# thermister-led.net
KiCad netlist of a schematic drawn in EAGLE
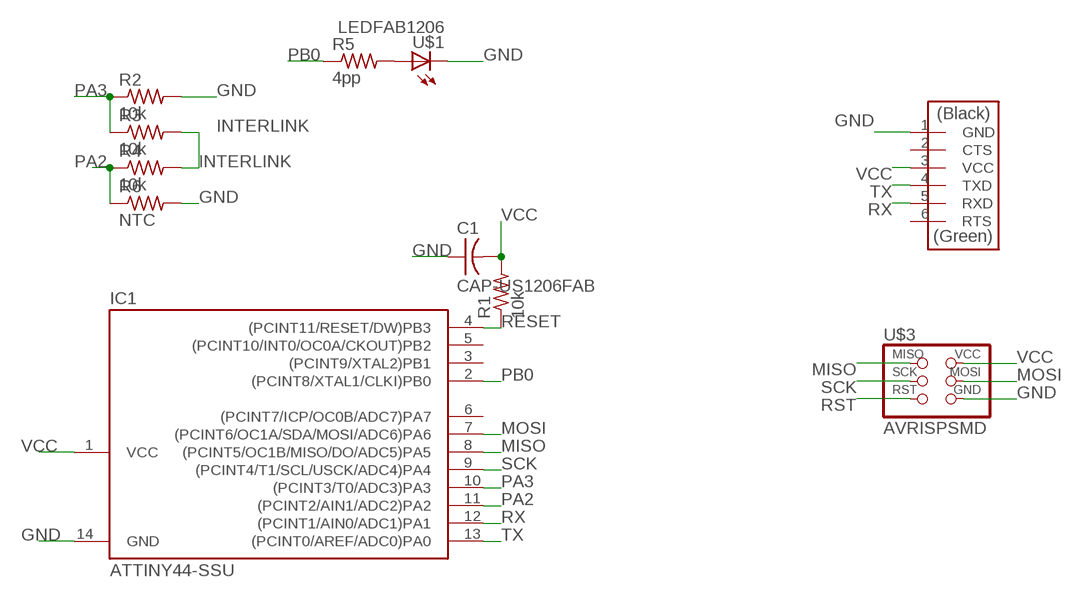
[diagram p0: schematic, sheet 1]

(export (version "E")
  (design (tool "Eeschema 10.0.6"))
  (components
    (comp (ref "C1")
      (value "CAP-US1206FAB")
      (footprint "eagle-import:C1206FAB")
      (libsource (lib "eagle-import") (part "CAP-US1206FAB"))
    )
    (comp (ref "IC1")
      (value "ATTINY44-SSU")
      (footprint "eagle-import:SOIC14")
      (libsource (lib "eagle-import") (part "ATTINY44-SSU"))
    )
    (comp (ref "R1")
      (value "10k")
      (footprint "eagle-import:R1206FAB")
      (libsource (lib "eagle-import") (part "RES-US1206FAB"))
    )
    (comp (ref "R2")
      (value "10k")
      (footprint "eagle-import:R1206FAB")
      (libsource (lib "eagle-import") (part "RES-US1206FAB"))
    )
    (comp (ref "R3")
      (value "10k")
      (footprint "eagle-import:R1206FAB")
      (libsource (lib "eagle-import") (part "RES-US1206FAB"))
    )
    (comp (ref "R4")
      (value "10k")
      (footprint "eagle-import:R1206FAB")
      (libsource (lib "eagle-import") (part "RES-US1206FAB"))
    )
    (comp (ref "R5")
      (value "4pp")
      (footprint "eagle-import:R1206FAB")
      (libsource (lib "eagle-import") (part "RES-US1206FAB"))
    )
    (comp (ref "R6")
      (value "NTC")
      (footprint "eagle-import:R1206FAB")
      (libsource (lib "eagle-import") (part "RES-US1206FAB"))
    )
    (comp (ref "U$1")
      (value "LEDFAB1206")
      (footprint "eagle-import:LED1206FAB")
      (libsource (lib "eagle-import") (part "LEDFAB1206"))
    )
    (comp (ref "U$2")
      (value "FTDI-SMD-HEADER")
      (footprint "eagle-import:1X06SMD")
      (libsource (lib "eagle-import") (part "FTDI-SMD-HEADER"))
    )
    (comp (ref "U$3")
      (value "AVRISPSMD")
      (footprint "eagle-import:2X03SMD")
      (libsource (lib "eagle-import") (part "AVRISPSMD"))
    )
  )
  (nets
    (net (code "1") (name "/GND") (class "Default")
      (node (ref "C1") (pin "1") (pinfunction "1_1") (pintype "passive"))
      (node (ref "IC1") (pin "14") (pinfunction "GND_14") (pintype "power_in"))
      (node (ref "R2") (pin "2") (pinfunction "2_2") (pintype "passive"))
      (node (ref "R6") (pin "2") (pinfunction "2_2") (pintype "passive"))
      (node (ref "U$1") (pin "2") (pinfunction "C_2") (pintype "passive"))
      (node (ref "U$2") (pin "1") (pinfunction "GND_1") (pintype "bidirectional"))
      (node (ref "U$3") (pin "6") (pinfunction "GND_6") (pintype "passive"))
    )
    (net (code "2") (name "/INTERLINK") (class "Default")
      (node (ref "R3") (pin "2") (pinfunction "2_2") (pintype "passive"))
      (node (ref "R4") (pin "2") (pinfunction "2_2") (pintype "passive"))
    )
    (net (code "3") (name "/MISO") (class "Default")
      (node (ref "IC1") (pin "8") (pinfunction "(PCINT5/OC1B/MISO/DO/ADC5)PA5_8") (pintype "bidirectional"))
      (node (ref "U$3") (pin "1") (pinfunction "MISO_1") (pintype "passive"))
    )
    (net (code "4") (name "/MOSI") (class "Default")
      (node (ref "IC1") (pin "7") (pinfunction "(PCINT6/OC1A/SDA/MOSI/ADC6)PA6_7") (pintype "bidirectional"))
      (node (ref "U$3") (pin "4") (pinfunction "MOSI_4") (pintype "passive"))
    )
    (net (code "5") (name "/PA2") (class "Default")
      (node (ref "IC1") (pin "11") (pinfunction "(PCINT2/AIN1/ADC2)PA2_11") (pintype "bidirectional"))
      (node (ref "R4") (pin "1") (pinfunction "1_1") (pintype "passive"))
      (node (ref "R6") (pin "1") (pinfunction "1_1") (pintype "passive"))
    )
    (net (code "6") (name "/PA3") (class "Default")
      (node (ref "IC1") (pin "10") (pinfunction "(PCINT3/T0/ADC3)PA3_10") (pintype "bidirectional"))
      (node (ref "R2") (pin "1") (pinfunction "1_1") (pintype "passive"))
      (node (ref "R3") (pin "1") (pinfunction "1_1") (pintype "passive"))
    )
    (net (code "7") (name "/PB0") (class "Default")
      (node (ref "IC1") (pin "2") (pinfunction "(PCINT8/XTAL1/CLKI)PB0_2") (pintype "bidirectional"))
      (node (ref "R5") (pin "1") (pinfunction "1_1") (pintype "passive"))
    )
    (net (code "8") (name "/RESET") (class "Default")
      (node (ref "IC1") (pin "4") (pinfunction "(PCINT11/RESET/DW)PB3_4") (pintype "bidirectional"))
      (node (ref "R1") (pin "1") (pinfunction "1_1") (pintype "passive"))
    )
    (net (code "9") (name "/RST") (class "Default")
      (node (ref "U$3") (pin "5") (pinfunction "RST_5") (pintype "passive"))
    )
    (net (code "10") (name "/RX") (class "Default")
      (node (ref "IC1") (pin "12") (pinfunction "(PCINT1/AIN0/ADC1)PA1_12") (pintype "bidirectional"))
      (node (ref "U$2") (pin "5") (pinfunction "RXD_5") (pintype "bidirectional"))
    )
    (net (code "11") (name "/SCK") (class "Default")
      (node (ref "IC1") (pin "9") (pinfunction "(PCINT4/T1/SCL/USCK/ADC4)PA4_9") (pintype "bidirectional"))
      (node (ref "U$3") (pin "3") (pinfunction "SCK_3") (pintype "passive"))
    )
    (net (code "12") (name "/TX") (class "Default")
      (node (ref "IC1") (pin "13") (pinfunction "(PCINT0/AREF/ADC0)PA0_13") (pintype "bidirectional"))
      (node (ref "U$2") (pin "4") (pinfunction "TXD_4") (pintype "bidirectional"))
    )
    (net (code "13") (name "/VCC") (class "Default")
      (node (ref "C1") (pin "2") (pinfunction "2_2") (pintype "passive"))
      (node (ref "IC1") (pin "1") (pinfunction "VCC_1") (pintype "power_in"))
      (node (ref "R1") (pin "2") (pinfunction "2_2") (pintype "passive"))
      (node (ref "U$2") (pin "3") (pinfunction "VCC_3") (pintype "bidirectional"))
      (node (ref "U$3") (pin "2") (pinfunction "VCC_2") (pintype "passive"))
    )
    (net (code "14") (name "Net-(U$1-A)") (class "Default")
      (node (ref "R5") (pin "2") (pinfunction "2_2") (pintype "passive"))
      (node (ref "U$1") (pin "1") (pinfunction "A_1") (pintype "passive"))
    )
    (net (code "15") (name "unconnected-(IC1-(PCINT7{slash}ICP{slash}OC0B{slash}ADC7)PA7-Pad6)") (class "Default")
      (node (ref "IC1") (pin "6") (pinfunction "(PCINT7/ICP/OC0B/ADC7)PA7_6") (pintype "bidirectional"))
    )
    (net (code "16") (name "unconnected-(IC1-(PCINT9{slash}XTAL2)PB1-Pad3)") (class "Default")
      (node (ref "IC1") (pin "3") (pinfunction "(PCINT9/XTAL2)PB1_3") (pintype "bidirectional"))
    )
    (net (code "17") (name "unconnected-(IC1-(PCINT10{slash}INT0{slash}OC0A{slash}CKOUT)PB2-Pad5)") (class "Default")
      (node (ref "IC1") (pin "5") (pinfunction "(PCINT10/INT0/OC0A/CKOUT)PB2_5") (pintype "bidirectional"))
    )
    (net (code "18") (name "unconnected-(U$2-CTS-Pad2)") (class "Default")
      (node (ref "U$2") (pin "2") (pinfunction "CTS_2") (pintype "bidirectional"))
    )
    (net (code "19") (name "unconnected-(U$2-RTS-Pad6)") (class "Default")
      (node (ref "U$2") (pin "6") (pinfunction "RTS_6") (pintype "bidirectional"))
    )
  )
)
